# ARDUINO_IO.net
KiCad netlist of a schematic drawn in Altium Designer
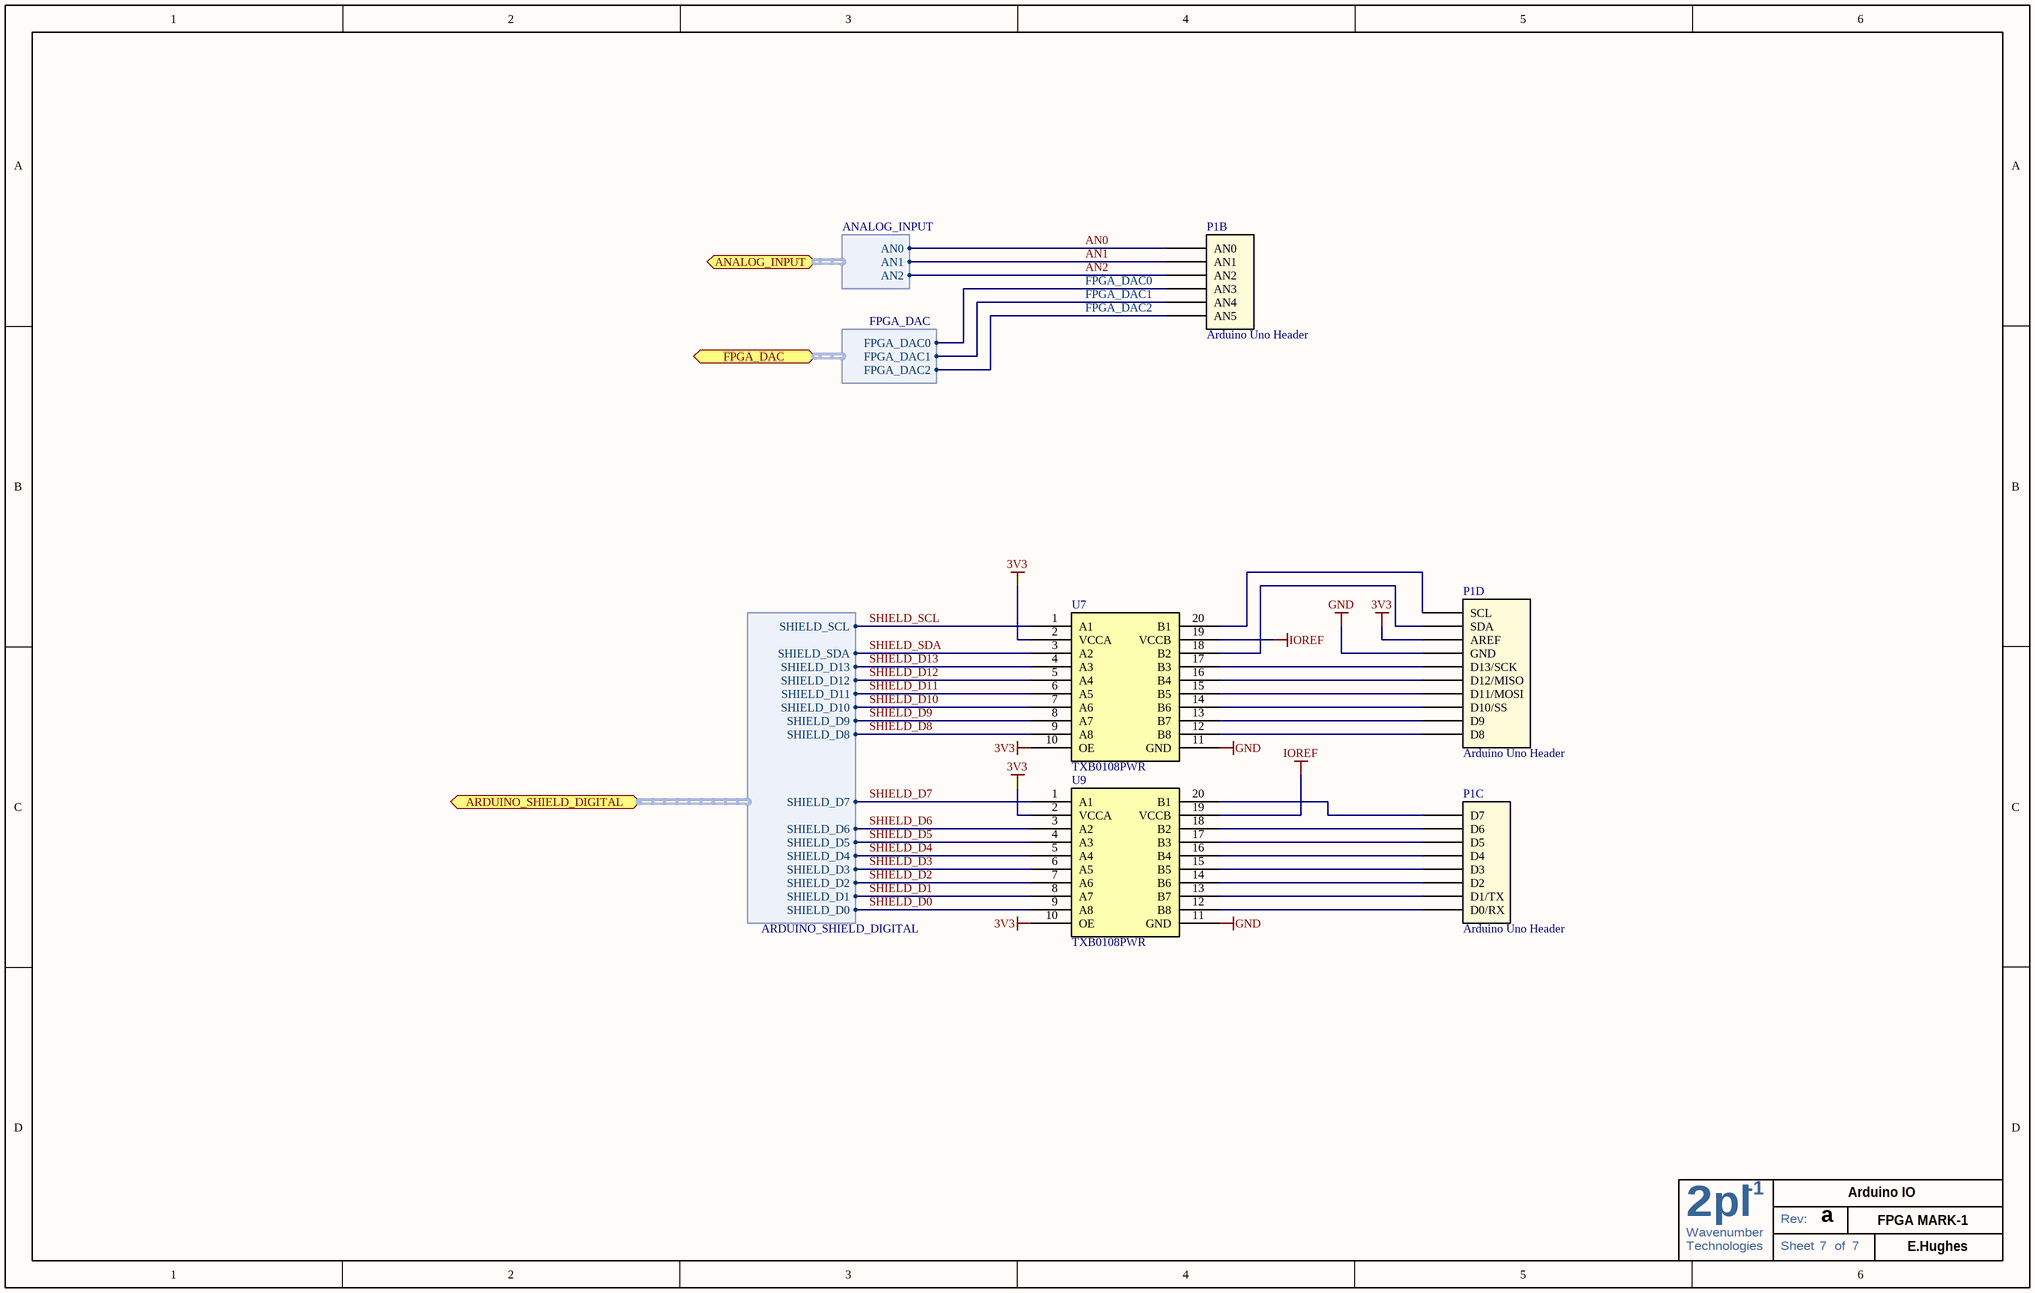
[diagram p0: ARDUINO_IO.SchDoc]

(export (version "E")
  (design (tool "Eeschema 10.0.6"))
  (components
    (comp (ref "P1")
      (value "Arduino Uno Header")
      (footprint "Arduino Shield - smaller Thru")
      (description "Arduino Duem Header")
      (libsource (lib "eConnector") (part "Arduino Shield"))
    )
    (comp (ref "U7")
      (value "TXB0108PWR")
      (footprint "TSSOP20")
      (description "IC 8-BIT TRNSTR 15KV ESD 20TSSOP")
      (fields (field (name "MANUFACTURER") "Texas Instruments"))
      (libsource (lib "eIC") (part "TXB0108PWR"))
    )
    (comp (ref "U9")
      (value "TXB0108PWR")
      (footprint "TSSOP20")
      (description "IC 8-BIT TRNSTR 15KV ESD 20TSSOP")
      (fields (field (name "MANUFACTURER") "Texas Instruments"))
      (libsource (lib "eIC") (part "TXB0108PWR"))
    )
  )
  (nets
    (net (code "4") (name "/AN0") (class "Default")
      (node (ref "P1") (pin "B1") (pinfunction "AN0_B1") (pintype "passive"))
    )
    (net (code "5") (name "/AN1") (class "Default")
      (node (ref "P1") (pin "B2") (pinfunction "AN1_B2") (pintype "passive"))
    )
    (net (code "6") (name "/AN2") (class "Default")
      (node (ref "P1") (pin "B3") (pinfunction "AN2_B3") (pintype "passive"))
    )
    (net (code "7") (name "/FPGA_DAC0") (class "Default")
      (node (ref "P1") (pin "B4") (pinfunction "AN3_B4") (pintype "passive"))
    )
    (net (code "8") (name "/FPGA_DAC1") (class "Default")
      (node (ref "P1") (pin "B5") (pinfunction "AN4_B5") (pintype "passive"))
    )
    (net (code "9") (name "/FPGA_DAC2") (class "Default")
      (node (ref "P1") (pin "B6") (pinfunction "AN5_B6") (pintype "passive"))
    )
    (net (code "10") (name "/SHIELD_D0") (class "Default")
      (node (ref "U9") (pin "9") (pinfunction "A8_9") (pintype "passive"))
    )
    (net (code "11") (name "/SHIELD_D1") (class "Default")
      (node (ref "U9") (pin "8") (pinfunction "A7_8") (pintype "passive"))
    )
    (net (code "12") (name "/SHIELD_D2") (class "Default")
      (node (ref "U9") (pin "7") (pinfunction "A6_7") (pintype "passive"))
    )
    (net (code "13") (name "/SHIELD_D3") (class "Default")
      (node (ref "U9") (pin "6") (pinfunction "A5_6") (pintype "passive"))
    )
    (net (code "14") (name "/SHIELD_D4") (class "Default")
      (node (ref "U9") (pin "5") (pinfunction "A4_5") (pintype "passive"))
    )
    (net (code "15") (name "/SHIELD_D5") (class "Default")
      (node (ref "U9") (pin "4") (pinfunction "A3_4") (pintype "passive"))
    )
    (net (code "16") (name "/SHIELD_D6") (class "Default")
      (node (ref "U9") (pin "3") (pinfunction "A2_3") (pintype "passive"))
    )
    (net (code "17") (name "/SHIELD_D7") (class "Default")
      (node (ref "U9") (pin "1") (pinfunction "A1_1") (pintype "passive"))
    )
    (net (code "18") (name "/SHIELD_D8") (class "Default")
      (node (ref "U7") (pin "9") (pinfunction "A8_9") (pintype "passive"))
    )
    (net (code "19") (name "/SHIELD_D9") (class "Default")
      (node (ref "U7") (pin "8") (pinfunction "A7_8") (pintype "passive"))
    )
    (net (code "20") (name "/SHIELD_D10") (class "Default")
      (node (ref "U7") (pin "7") (pinfunction "A6_7") (pintype "passive"))
    )
    (net (code "21") (name "/SHIELD_D11") (class "Default")
      (node (ref "U7") (pin "6") (pinfunction "A5_6") (pintype "passive"))
    )
    (net (code "22") (name "/SHIELD_D12") (class "Default")
      (node (ref "U7") (pin "5") (pinfunction "A4_5") (pintype "passive"))
    )
    (net (code "23") (name "/SHIELD_D13") (class "Default")
      (node (ref "U7") (pin "4") (pinfunction "A3_4") (pintype "passive"))
    )
    (net (code "24") (name "/SHIELD_SCL") (class "Default")
      (node (ref "U7") (pin "1") (pinfunction "A1_1") (pintype "passive"))
    )
    (net (code "25") (name "/SHIELD_SDA") (class "Default")
      (node (ref "U7") (pin "3") (pinfunction "A2_3") (pintype "passive"))
    )
    (net (code "29") (name "3V3") (class "Default")
      (node (ref "P1") (pin "D8") (pinfunction "AREF_D8") (pintype "passive"))
      (node (ref "U7") (pin "10") (pinfunction "OE_10") (pintype "passive"))
      (node (ref "U7") (pin "2") (pinfunction "VCCA_2") (pintype "passive"))
      (node (ref "U9") (pin "10") (pinfunction "OE_10") (pintype "passive"))
      (node (ref "U9") (pin "2") (pinfunction "VCCA_2") (pintype "passive"))
    )
    (net (code "30") (name "GND") (class "Default")
      (node (ref "P1") (pin "D7") (pinfunction "GND_D7") (pintype "passive"))
      (node (ref "U7") (pin "11") (pinfunction "GND_11") (pintype "passive"))
      (node (ref "U9") (pin "11") (pinfunction "GND_11") (pintype "passive"))
    )
    (net (code "31") (name "IOREF") (class "Default")
      (node (ref "U7") (pin "19") (pinfunction "VCCB_19") (pintype "passive"))
      (node (ref "U9") (pin "19") (pinfunction "VCCB_19") (pintype "passive"))
    )
    (net (code "32") (name "Net-(P1C-D0{slash}RX)") (class "Default")
      (node (ref "P1") (pin "C1") (pinfunction "D0/RX_C1") (pintype "passive"))
      (node (ref "U9") (pin "12") (pinfunction "B8_12") (pintype "passive"))
    )
    (net (code "33") (name "Net-(P1C-D1{slash}TX)") (class "Default")
      (node (ref "P1") (pin "C2") (pinfunction "D1/TX_C2") (pintype "passive"))
      (node (ref "U9") (pin "13") (pinfunction "B7_13") (pintype "passive"))
    )
    (net (code "34") (name "Net-(P1C-D2)") (class "Default")
      (node (ref "P1") (pin "C3") (pinfunction "D2_C3") (pintype "passive"))
      (node (ref "U9") (pin "14") (pinfunction "B6_14") (pintype "passive"))
    )
    (net (code "35") (name "Net-(P1C-D3)") (class "Default")
      (node (ref "P1") (pin "C4") (pinfunction "D3_C4") (pintype "passive"))
      (node (ref "U9") (pin "15") (pinfunction "B5_15") (pintype "passive"))
    )
    (net (code "36") (name "Net-(P1C-D4)") (class "Default")
      (node (ref "P1") (pin "C5") (pinfunction "D4_C5") (pintype "passive"))
      (node (ref "U9") (pin "16") (pinfunction "B4_16") (pintype "passive"))
    )
    (net (code "37") (name "Net-(P1C-D5)") (class "Default")
      (node (ref "P1") (pin "C6") (pinfunction "D5_C6") (pintype "passive"))
      (node (ref "U9") (pin "17") (pinfunction "B3_17") (pintype "passive"))
    )
    (net (code "38") (name "Net-(P1C-D6)") (class "Default")
      (node (ref "P1") (pin "C7") (pinfunction "D6_C7") (pintype "passive"))
      (node (ref "U9") (pin "18") (pinfunction "B2_18") (pintype "passive"))
    )
    (net (code "39") (name "Net-(P1C-D7)") (class "Default")
      (node (ref "P1") (pin "C8") (pinfunction "D7_C8") (pintype "passive"))
      (node (ref "U9") (pin "20") (pinfunction "B1_20") (pintype "passive"))
    )
    (net (code "40") (name "Net-(P1D-D8)") (class "Default")
      (node (ref "P1") (pin "D1") (pinfunction "D8_D1") (pintype "passive"))
      (node (ref "U7") (pin "12") (pinfunction "B8_12") (pintype "passive"))
    )
    (net (code "41") (name "Net-(P1D-D9)") (class "Default")
      (node (ref "P1") (pin "D2") (pinfunction "D9_D2") (pintype "passive"))
      (node (ref "U7") (pin "13") (pinfunction "B7_13") (pintype "passive"))
    )
    (net (code "42") (name "Net-(P1D-D10{slash}SS)") (class "Default")
      (node (ref "P1") (pin "D3") (pinfunction "D10/SS_D3") (pintype "passive"))
      (node (ref "U7") (pin "14") (pinfunction "B6_14") (pintype "passive"))
    )
    (net (code "43") (name "Net-(P1D-D11{slash}MOSI)") (class "Default")
      (node (ref "P1") (pin "D4") (pinfunction "D11/MOSI_D4") (pintype "passive"))
      (node (ref "U7") (pin "15") (pinfunction "B5_15") (pintype "passive"))
    )
    (net (code "44") (name "Net-(P1D-D12{slash}MISO)") (class "Default")
      (node (ref "P1") (pin "D5") (pinfunction "D12/MISO_D5") (pintype "passive"))
      (node (ref "U7") (pin "16") (pinfunction "B4_16") (pintype "passive"))
    )
    (net (code "45") (name "Net-(P1D-D13{slash}SCK)") (class "Default")
      (node (ref "P1") (pin "D6") (pinfunction "D13/SCK_D6") (pintype "passive"))
      (node (ref "U7") (pin "17") (pinfunction "B3_17") (pintype "passive"))
    )
    (net (code "46") (name "Net-(P1D-SCL)") (class "Default")
      (node (ref "P1") (pin "D10") (pinfunction "SCL_D10") (pintype "passive"))
      (node (ref "U7") (pin "20") (pinfunction "B1_20") (pintype "passive"))
    )
    (net (code "47") (name "Net-(P1D-SDA)") (class "Default")
      (node (ref "P1") (pin "D9") (pinfunction "SDA_D9") (pintype "passive"))
      (node (ref "U7") (pin "18") (pinfunction "B2_18") (pintype "passive"))
    )
  )
)
